# Power.net
KiCad netlist of a schematic drawn in Altium Designer
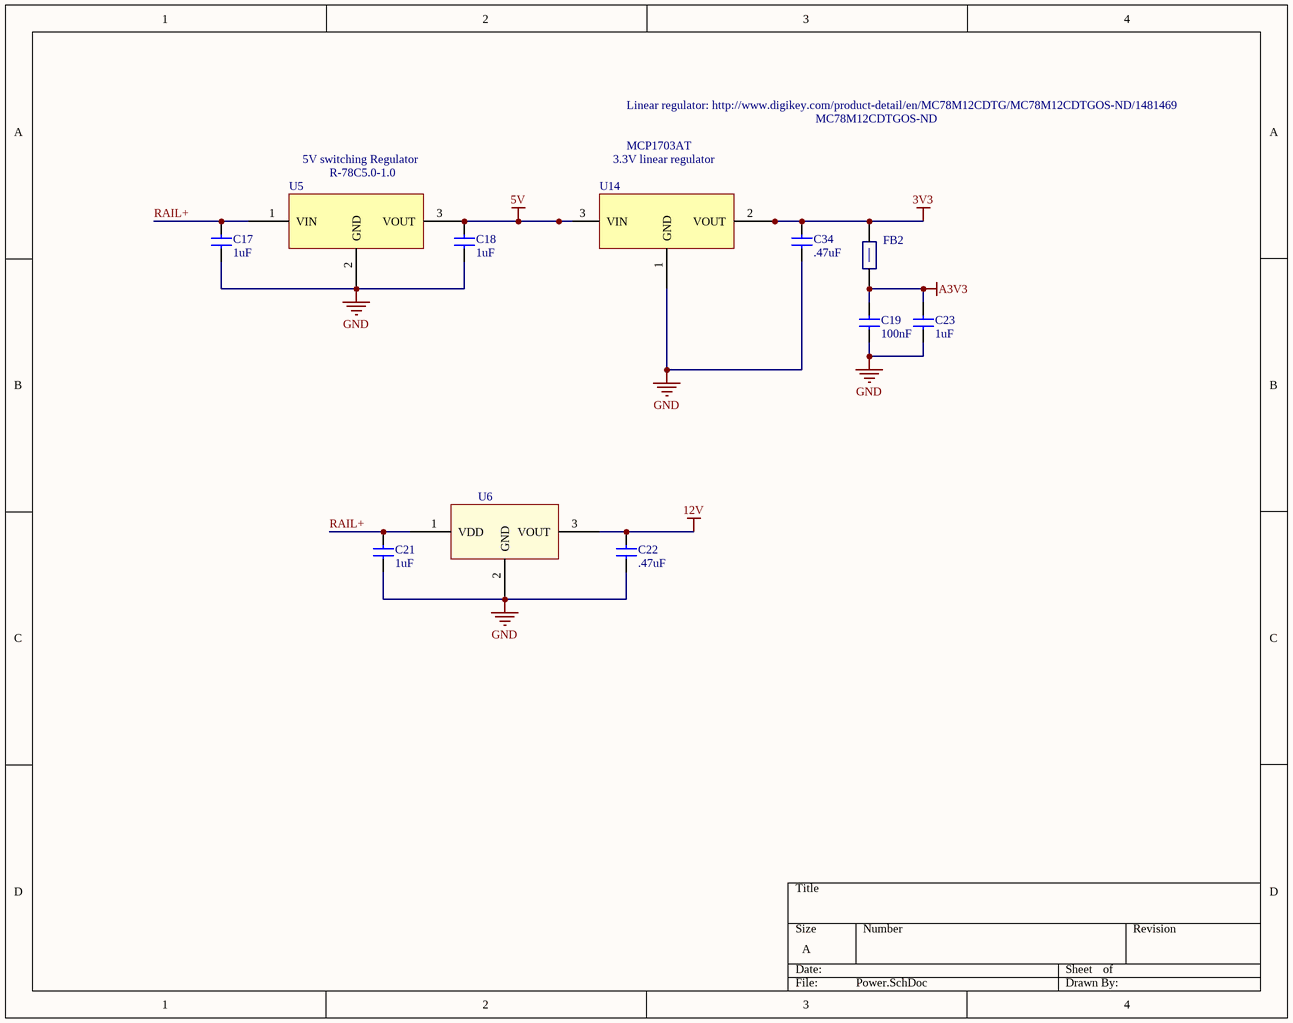
[diagram p0: Power.SchDoc]

(export (version "E")
  (design (tool "Eeschema 10.0.6"))
  (components
    (comp (ref "C17")
      (value "1uF")
      (footprint "CAPC0603")
      (fields (field (name "Comment") "Cap"))
      (libsource (lib "SubjuGator8") (part "Cap"))
    )
    (comp (ref "C18")
      (value "1uF")
      (footprint "CAPC0603")
      (fields (field (name "Comment") "Cap"))
      (libsource (lib "SubjuGator8") (part "Cap"))
    )
    (comp (ref "C19")
      (value "100nF")
      (footprint "CAPC0603")
      (fields (field (name "Comment") "Cap"))
      (libsource (lib "SubjuGator8") (part "Cap"))
    )
    (comp (ref "C21")
      (value "1uF")
      (footprint "CAPC0603")
      (fields (field (name "Comment") "Cap"))
      (libsource (lib "SubjuGator8") (part "Cap"))
    )
    (comp (ref "C22")
      (value ".47uF")
      (footprint "CAPC0603")
      (fields (field (name "Comment") "Cap"))
      (libsource (lib "SubjuGator8") (part "Cap"))
    )
    (comp (ref "C23")
      (value "1uF")
      (footprint "CAPC0603")
      (fields (field (name "Comment") "Cap"))
      (libsource (lib "SubjuGator8") (part "Cap"))
    )
    (comp (ref "C34")
      (value ".47uF")
      (footprint "CAPC0603")
      (fields (field (name "Comment") "Cap"))
      (libsource (lib "SubjuGator8") (part "Cap"))
    )
    (comp (ref "FB2")
      (value "FBead")
      (footprint "RES0603")
      (description "Ferrite Bead")
      (libsource (lib "SubjuGator8") (part "FBead"))
    )
    (comp (ref "U5")
      (value "R-78C5.0-1.0")
      (footprint "R-78C5.0-1.0")
      (description "CONV DC/DC 1A 5V OUT SIP VERT")
      (libsource (lib "SubjuGator8") (part "R-78C5.0-1.0"))
    )
    (comp (ref "U6")
      (value "MC78M12CDTG")
      (footprint "MC78M12CDTG")
      (description "IC REG LDO 12V 0.5A DPAK")
      (libsource (lib "SubjuGator8") (part "MC78M12CDTG"))
    )
    (comp (ref "U14")
      (value "MCP1703AT")
      (footprint "MCP1703AT-xx02EMB")
      (description "250 mA, 16V, Low Quiescent Current LDO Regulator")
      (libsource (lib "SubjuGator8") (part "MCP1703AT"))
    )
  )
  (nets
    (net (code "1") (name "/RAIL+") (class "Default")
      (node (ref "C17") (pin "1") (pinfunction "A_1") (pintype "passive"))
      (node (ref "C21") (pin "1") (pinfunction "A_1") (pintype "passive"))
      (node (ref "U5") (pin "1") (pinfunction "VIN_1") (pintype "passive"))
      (node (ref "U6") (pin "1") (pinfunction "VDD_1") (pintype "power_in"))
    )
    (net (code "2") (name "3V3") (class "Default")
      (node (ref "C34") (pin "1") (pinfunction "A_1") (pintype "passive"))
      (node (ref "FB2") (pin "2") (pinfunction "B_2") (pintype "passive"))
      (node (ref "U14") (pin "2") (pinfunction "VOUT_2") (pintype "passive"))
    )
    (net (code "3") (name "5V") (class "Default")
      (node (ref "C18") (pin "1") (pinfunction "A_1") (pintype "passive"))
      (node (ref "U14") (pin "3") (pinfunction "VIN_3") (pintype "passive"))
      (node (ref "U5") (pin "3") (pinfunction "VOUT_3") (pintype "passive"))
    )
    (net (code "4") (name "12V") (class "Default")
      (node (ref "C22") (pin "1") (pinfunction "A_1") (pintype "passive"))
      (node (ref "U6") (pin "3") (pinfunction "VOUT_3") (pintype "power_in"))
    )
    (net (code "5") (name "A3V3") (class "Default")
      (node (ref "C19") (pin "1") (pinfunction "A_1") (pintype "passive"))
      (node (ref "C23") (pin "1") (pinfunction "A_1") (pintype "passive"))
      (node (ref "FB2") (pin "1") (pinfunction "A_1") (pintype "passive"))
    )
    (net (code "6") (name "GND") (class "Default")
      (node (ref "C17") (pin "2") (pinfunction "B_2") (pintype "passive"))
      (node (ref "C18") (pin "2") (pinfunction "B_2") (pintype "passive"))
      (node (ref "C19") (pin "2") (pinfunction "B_2") (pintype "passive"))
      (node (ref "C21") (pin "2") (pinfunction "B_2") (pintype "passive"))
      (node (ref "C22") (pin "2") (pinfunction "B_2") (pintype "passive"))
      (node (ref "C23") (pin "2") (pinfunction "B_2") (pintype "passive"))
      (node (ref "C34") (pin "2") (pinfunction "B_2") (pintype "passive"))
      (node (ref "U14") (pin "1") (pinfunction "GND_1") (pintype "power_in"))
      (node (ref "U5") (pin "2") (pinfunction "GND_2") (pintype "power_in"))
      (node (ref "U6") (pin "2") (pinfunction "GND_2") (pintype "power_in"))
    )
  )
)
